# Power.net
KiCad netlist of a schematic drawn in Altium Designer
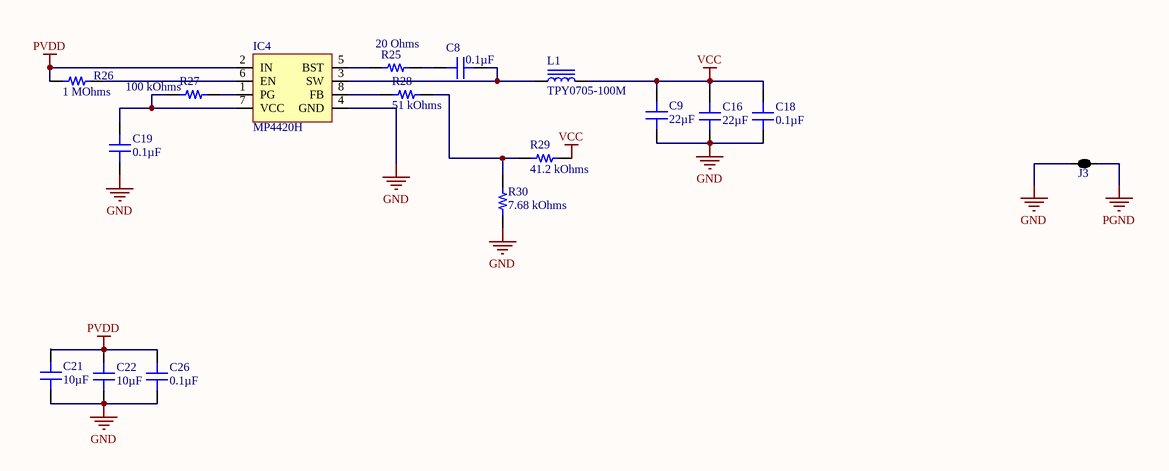
[diagram p0: Power.SchDoc]

(export (version "E")
  (design (tool "Eeschema 10.0.6"))
  (components
    (comp (ref "C8")
      (value "0.1µF")
      (footprint "CAP 0603_1608")
      (description "CAP CER 0.1UF 50V X7R 0603")
      (fields
        (field (name "PART NUMBER") "CML0603X7R104KT50V")
        (field (name "MANUFACTURER") "Stackpole Electronics Inc")
      )
      (libsource (lib "Celestial Altium Library - altium_library") (part "Capacitor"))
    )
    (comp (ref "C9")
      (value "22µF")
      (footprint "CAP 1210_3225 - 1MM")
      (description "CAP CER 22UF 16V X5R 1210")
      (fields (field (name "PART NUMBER") "EMK325BJ226MD-T") (field (name "MANUFACTURER") "Taiyo Yuden"))
      (libsource (lib "Celestial Altium Library - altium_library") (part "Capacitor"))
    )
    (comp (ref "C16")
      (value "22µF")
      (footprint "CAP 1210_3225 - 1MM")
      (description "CAP CER 22UF 16V X5R 1210")
      (fields (field (name "PART NUMBER") "EMK325BJ226MD-T") (field (name "MANUFACTURER") "Taiyo Yuden"))
      (libsource (lib "Celestial Altium Library - altium_library") (part "Capacitor"))
    )
    (comp (ref "C18")
      (value "0.1µF")
      (footprint "CAP 0603_1608")
      (description "CAP CER 0.1UF 50V X7R 0603")
      (fields
        (field (name "PART NUMBER") "CML0603X7R104KT50V")
        (field (name "MANUFACTURER") "Stackpole Electronics Inc")
      )
      (libsource (lib "Celestial Altium Library - altium_library") (part "Capacitor"))
    )
    (comp (ref "C19")
      (value "0.1µF")
      (footprint "CAP 0603_1608")
      (description "CAP CER 0.1UF 50V X7R 0603")
      (fields
        (field (name "PART NUMBER") "CML0603X7R104KT50V")
        (field (name "MANUFACTURER") "Stackpole Electronics Inc")
      )
      (libsource (lib "Celestial Altium Library - altium_library") (part "Capacitor"))
    )
    (comp (ref "C21")
      (value "10µF")
      (footprint "CAP 1210_3225 - 1.8MM")
      (description "CAP CER 10UF 50V X5R 1210")
      (fields
        (field (name "PART NUMBER") "1210BW106K500NGX110T")
        (field (name "MANUFACTURER") "Knowles Novacap")
      )
      (libsource (lib "Celestial Altium Library - altium_library") (part "Capacitor"))
    )
    (comp (ref "C22")
      (value "10µF")
      (footprint "CAP 1210_3225 - 1.8MM")
      (description "CAP CER 10UF 50V X5R 1210")
      (fields
        (field (name "PART NUMBER") "1210BW106K500NGX110T")
        (field (name "MANUFACTURER") "Knowles Novacap")
      )
      (libsource (lib "Celestial Altium Library - altium_library") (part "Capacitor"))
    )
    (comp (ref "C26")
      (value "0.1µF")
      (footprint "CAP 0603_1608")
      (description "CAP CER 0.1UF 50V X7R 0603")
      (fields
        (field (name "PART NUMBER") "CML0603X7R104KT50V")
        (field (name "MANUFACTURER") "Stackpole Electronics Inc")
      )
      (libsource (lib "Celestial Altium Library - altium_library") (part "Capacitor"))
    )
    (comp (ref "IC4")
      (value "MP4420H")
      (footprint "TSOT23-8")
      (description "V.REG.2A 3.8V-36V STEP-DOW TSOT-23-8")
      (libsource (lib "UserIntegrated") (part "MP4420H"))
    )
    (comp (ref "J3")
      (value "2 way net tie junction")
      (footprint "2way_HP")
      (libsource (lib "NetTieLib") (part "2way"))
    )
    (comp (ref "L1")
      (value "TPY0705-100M")
      (footprint "INDP6868X46N")
      (description "INDUCTOR FIXED 10UH 7X7MM SMD")
      (libsource (lib "UserIntegrated") (part "TPY0705-100M"))
    )
    (comp (ref "R25")
      (value "20 Ohms")
      (footprint "RES 0603_1608")
      (description "RES SMD 20 OHM 1% 1/10W 0603")
      (fields (field (name "PART NUMBER") "CRCW060320R0FKEB") (field (name "MANUFACTURER") "Vishay Dale"))
      (libsource (lib "Celestial Altium Library - altium_library") (part "Resistor"))
    )
    (comp (ref "R26")
      (value "1 MOhms")
      (footprint "RES 0603_1608")
      (description "RES SMD 1M OHM 5% 1/10W 0603")
      (fields (field (name "PART NUMBER") "KTR03EZPJ105") (field (name "MANUFACTURER") "Rohm Semiconductor"))
      (libsource (lib "Celestial Altium Library - altium_library") (part "Resistor"))
    )
    (comp (ref "R27")
      (value "100 kOhms")
      (footprint "RES 0603_1608")
      (description "RES SMD 100K OHM 5% 1/10W 0603")
      (fields (field (name "PART NUMBER") "CR0603-JW-104ELF") (field (name "MANUFACTURER") "Bourns Inc."))
      (libsource (lib "Celestial Altium Library - altium_library") (part "Resistor"))
    )
    (comp (ref "R28")
      (value "51 kOhms")
      (footprint "RES 0805_2012")
      (description "RES 51K OHM 0.1% 1/8W 0805")
      (fields
        (field (name "PART NUMBER") "RN73R2ATTD5102B25")
        (field (name "MANUFACTURER") "KOA Speer Electronics, Inc.")
      )
      (libsource (lib "Celestial Altium Library - altium_library") (part "Resistor"))
    )
    (comp (ref "R29")
      (value "41.2 kOhms")
      (footprint "RES 0805_2012")
      (description "RES SMD 41.2K OHM 1% 1/8W 0805")
      (fields
        (field (name "PART NUMBER") "ERJ-6ENF4122V")
        (field (name "MANUFACTURER") "Panasonic Electronic Components")
      )
      (libsource (lib "Celestial Altium Library - altium_library") (part "Resistor"))
    )
    (comp (ref "R30")
      (value "7.68 kOhms")
      (footprint "RES 0805_2012")
      (description "RES 7.68K OHM 0.1% 1/8W 0805")
      (fields
        (field (name "PART NUMBER") "ERA-6AEB7681V")
        (field (name "MANUFACTURER") "Panasonic Electronic Components")
      )
      (libsource (lib "Celestial Altium Library - altium_library") (part "Resistor"))
    )
  )
  (nets
    (net (code "1") (name "GND") (class "Default")
      (node (ref "C16") (pin "1") (pinfunction "1_1") (pintype "passive"))
      (node (ref "C18") (pin "1") (pinfunction "1_1") (pintype "passive"))
      (node (ref "C19") (pin "1") (pinfunction "1_1") (pintype "passive"))
      (node (ref "C21") (pin "1") (pinfunction "1_1") (pintype "passive"))
      (node (ref "C22") (pin "1") (pinfunction "1_1") (pintype "passive"))
      (node (ref "C26") (pin "1") (pinfunction "1_1") (pintype "passive"))
      (node (ref "C9") (pin "1") (pinfunction "1_1") (pintype "passive"))
      (node (ref "IC4") (pin "4") (pinfunction "GND_4") (pintype "passive"))
      (node (ref "J3") (pin "1") (pinfunction "1_1") (pintype "passive"))
      (node (ref "R30") (pin "1") (pinfunction "1_1") (pintype "passive"))
    )
    (net (code "2") (name "Net-(C8-Pad1)") (class "Default")
      (node (ref "C8") (pin "1") (pinfunction "1_1") (pintype "passive"))
      (node (ref "R25") (pin "2") (pinfunction "2_2") (pintype "passive"))
    )
    (net (code "3") (name "Net-(IC4-BST)") (class "Default")
      (node (ref "IC4") (pin "5") (pinfunction "BST_5") (pintype "passive"))
      (node (ref "R25") (pin "1") (pinfunction "1_1") (pintype "passive"))
    )
    (net (code "4") (name "Net-(IC4-EN)") (class "Default")
      (node (ref "IC4") (pin "6") (pinfunction "EN_6") (pintype "passive"))
      (node (ref "R26") (pin "2") (pinfunction "2_2") (pintype "passive"))
    )
    (net (code "5") (name "Net-(IC4-FB)") (class "Default")
      (node (ref "IC4") (pin "8") (pinfunction "FB_8") (pintype "passive"))
      (node (ref "R28") (pin "1") (pinfunction "1_1") (pintype "passive"))
    )
    (net (code "6") (name "Net-(IC4-PG)") (class "Default")
      (node (ref "IC4") (pin "1") (pinfunction "PG_1") (pintype "passive"))
      (node (ref "R27") (pin "2") (pinfunction "2_2") (pintype "passive"))
    )
    (net (code "7") (name "Net-(IC4-SW)") (class "Default")
      (node (ref "C8") (pin "2") (pinfunction "2_2") (pintype "passive"))
      (node (ref "IC4") (pin "3") (pinfunction "SW_3") (pintype "passive"))
      (node (ref "L1") (pin "1") (pinfunction "1_1") (pintype "passive"))
    )
    (net (code "8") (name "Net-(IC4-VCC)") (class "Default")
      (node (ref "C19") (pin "2") (pinfunction "2_2") (pintype "passive"))
      (node (ref "IC4") (pin "7") (pinfunction "VCC_7") (pintype "passive"))
      (node (ref "R27") (pin "1") (pinfunction "1_1") (pintype "passive"))
    )
    (net (code "9") (name "Net-(R28-Pad2)") (class "Default")
      (node (ref "R28") (pin "2") (pinfunction "2_2") (pintype "passive"))
      (node (ref "R29") (pin "1") (pinfunction "1_1") (pintype "passive"))
      (node (ref "R30") (pin "2") (pinfunction "2_2") (pintype "passive"))
    )
    (net (code "10") (name "PGND") (class "Default")
      (node (ref "J3") (pin "2") (pinfunction "2_2") (pintype "passive"))
    )
    (net (code "11") (name "PVDD") (class "Default")
      (node (ref "C21") (pin "2") (pinfunction "2_2") (pintype "passive"))
      (node (ref "C22") (pin "2") (pinfunction "2_2") (pintype "passive"))
      (node (ref "C26") (pin "2") (pinfunction "2_2") (pintype "passive"))
      (node (ref "IC4") (pin "2") (pinfunction "IN_2") (pintype "passive"))
      (node (ref "R26") (pin "1") (pinfunction "1_1") (pintype "passive"))
    )
    (net (code "12") (name "VCC") (class "Default")
      (node (ref "C16") (pin "2") (pinfunction "2_2") (pintype "passive"))
      (node (ref "C18") (pin "2") (pinfunction "2_2") (pintype "passive"))
      (node (ref "C9") (pin "2") (pinfunction "2_2") (pintype "passive"))
      (node (ref "L1") (pin "2") (pinfunction "2_2") (pintype "passive"))
      (node (ref "R29") (pin "2") (pinfunction "2_2") (pintype "passive"))
    )
  )
)
